# LED-Board.net
KiCad netlist of a schematic drawn in EAGLE
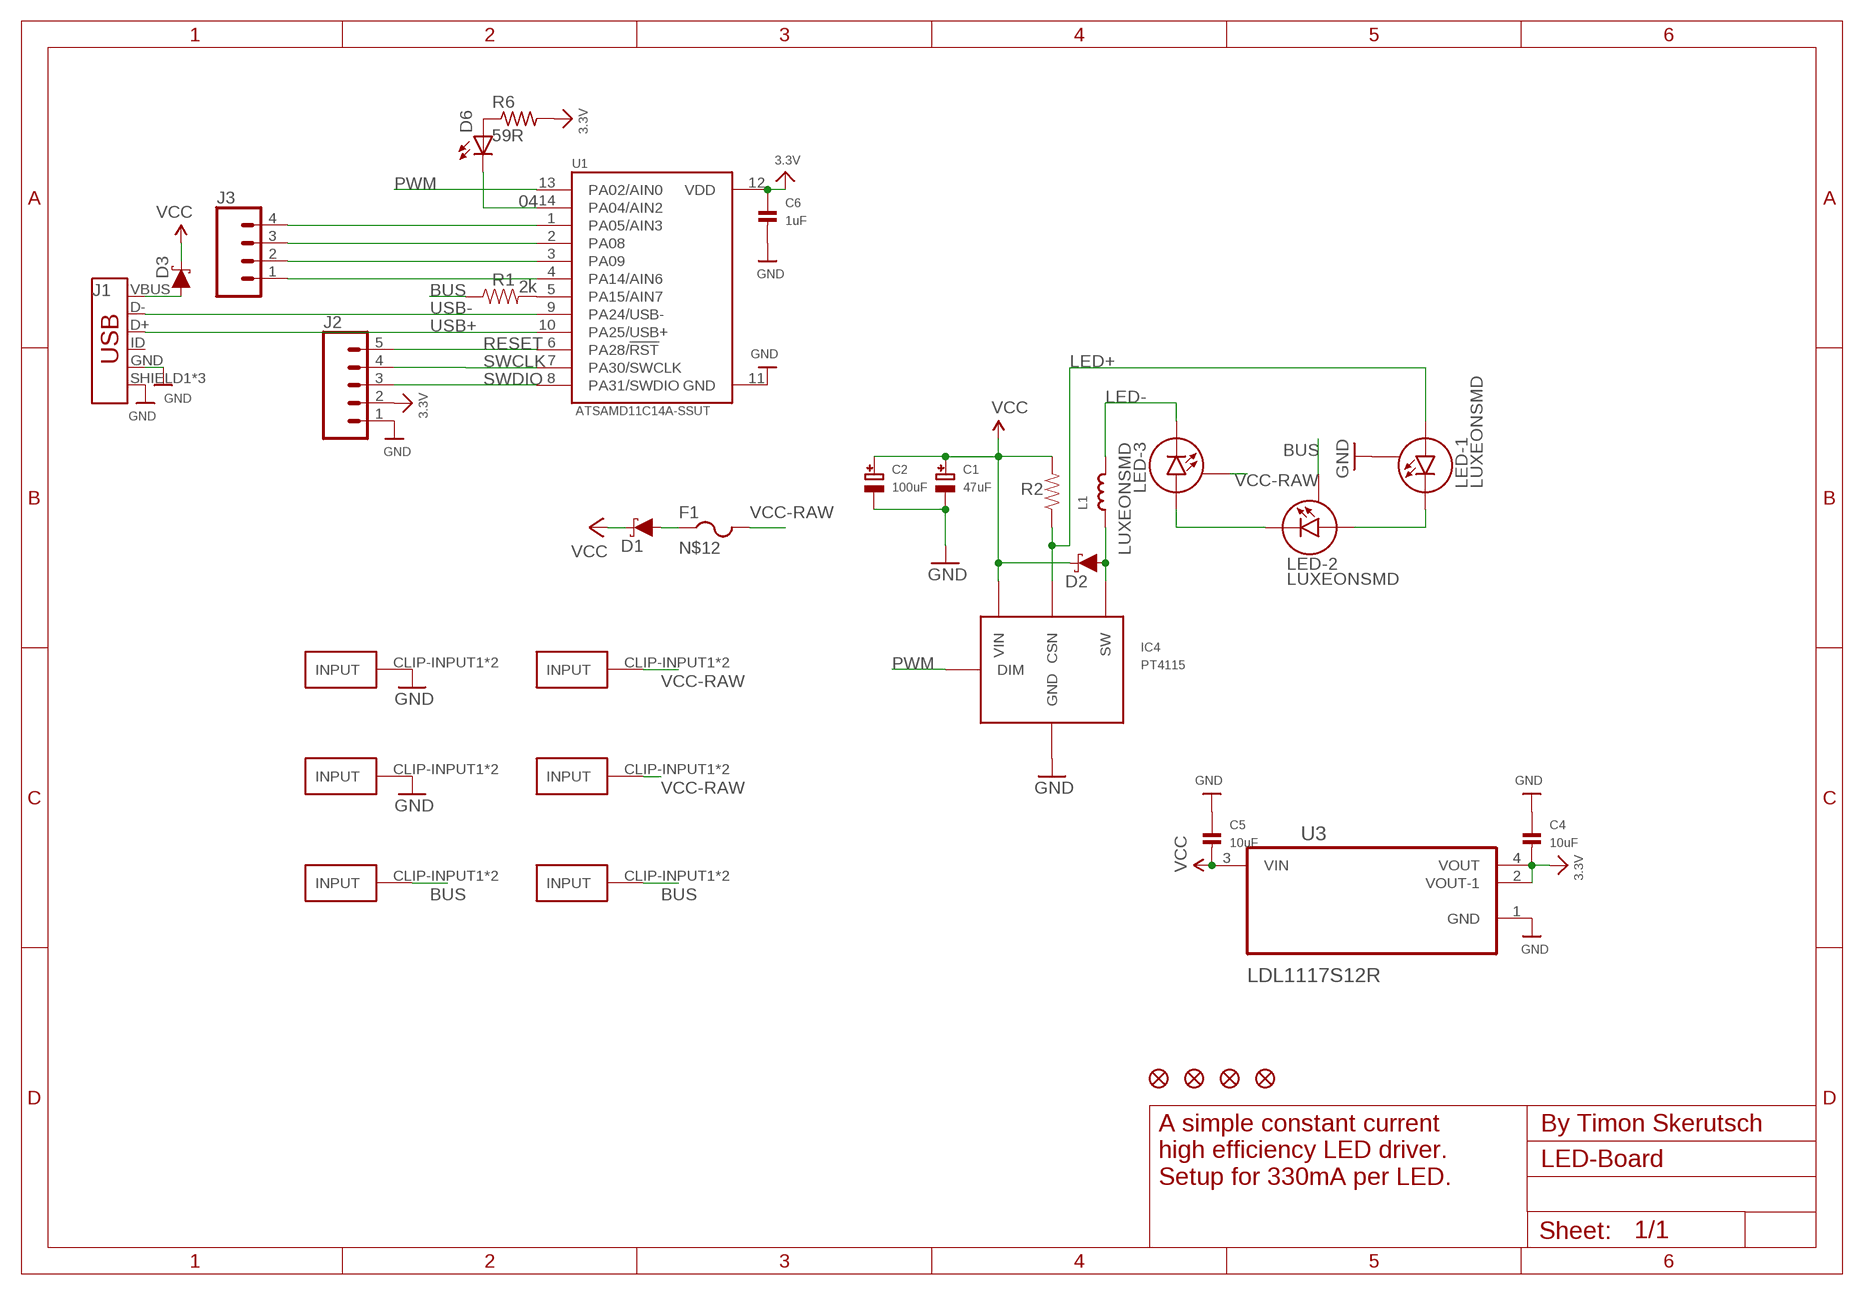
[diagram p0: schematic, sheet 1]

(export (version "E")
  (design (tool "Eeschema 10.0.6"))
  (components
    (comp (ref "C1")
      (value "47uF")
      (footprint "eagle-import:PANASONIC_D")
      (libsource (lib "eagle-import") (part "CAP_ELECTROLYTICPANASONIC_D"))
    )
    (comp (ref "C2")
      (value "100uF")
      (footprint "eagle-import:PANASONIC_D")
      (libsource (lib "eagle-import") (part "CAP_ELECTROLYTICPANASONIC_D"))
    )
    (comp (ref "C4")
      (value "10uF")
      (footprint "eagle-import:0805")
      (libsource (lib "eagle-import") (part "CAP_CERAMIC0805"))
    )
    (comp (ref "C5")
      (value "10uF")
      (footprint "eagle-import:0603")
      (libsource (lib "eagle-import") (part "CAP_CERAMIC0603"))
    )
    (comp (ref "C6")
      (value "1uF")
      (footprint "eagle-import:0603")
      (libsource (lib "eagle-import") (part "CAP_CERAMIC0603"))
    )
    (comp (ref "D1")
      (value "3A/40V/500mV")
      (footprint "eagle-import:SMA-DIODE")
      (libsource (lib "eagle-import") (part "DIODE-SCHOTTKY-B340A"))
    )
    (comp (ref "D2")
      (value "3A/40V/500mV")
      (footprint "eagle-import:SMA-DIODE")
      (libsource (lib "eagle-import") (part "DIODE-SCHOTTKY-B340A"))
    )
    (comp (ref "D3")
      (value "3A/40V/500mV")
      (footprint "eagle-import:SMA-DIODE")
      (libsource (lib "eagle-import") (part "DIODE-SCHOTTKY-B340A"))
    )
    (comp (ref "D6")
      (value "LEDCHIPLED_0805")
      (footprint "eagle-import:CHIPLED_0805")
      (libsource (lib "eagle-import") (part "LEDCHIPLED_0805"))
    )
    (comp (ref "F1")
      (value "TLC-MSMD110/24")
      (footprint "eagle-import:1812")
      (libsource (lib "eagle-import") (part "PTCFUSE-1812"))
    )
    (comp (ref "FD1")
      (value "FIDUCIAL1X2")
      (footprint "eagle-import:FIDUCIAL-1X2")
      (libsource (lib "eagle-import") (part "FIDUCIAL1X2"))
    )
    (comp (ref "FD2")
      (value "FIDUCIAL1X2")
      (footprint "eagle-import:FIDUCIAL-1X2")
      (libsource (lib "eagle-import") (part "FIDUCIAL1X2"))
    )
    (comp (ref "FD3")
      (value "FIDUCIAL1X2")
      (footprint "eagle-import:FIDUCIAL-1X2")
      (libsource (lib "eagle-import") (part "FIDUCIAL1X2"))
    )
    (comp (ref "FD4")
      (value "FIDUCIAL1X2")
      (footprint "eagle-import:FIDUCIAL-1X2")
      (libsource (lib "eagle-import") (part "FIDUCIAL1X2"))
    )
    (comp (ref "GND-CLIP")
      (value "FUSE-HOLDER-5X20MM")
      (footprint "eagle-import:FUSE-HOLDER-5X20MM")
      (libsource (lib "eagle-import") (part "FUSE-HOLDER-5X20MM"))
    )
    (comp (ref "GND-CLIP3")
      (value "FUSE-HOLDER-5X20MM")
      (footprint "eagle-import:FUSE-HOLDER-5X20MM")
      (libsource (lib "eagle-import") (part "FUSE-HOLDER-5X20MM"))
    )
    (comp (ref "IC4")
      (value "PT4115")
      (footprint "eagle-import:PT4115")
      (libsource (lib "eagle-import") (part "PT4115"))
    )
    (comp (ref "J1")
      (value "USB_MICRO-B_FEMALE-SMT")
      (footprint "eagle-import:USB-B-MICRO-SMD")
      (libsource (lib "eagle-import") (part "USB_MICRO-B_FEMALE-SMT"))
    )
    (comp (ref "J2")
      (value "CONN_05")
      (footprint "eagle-import:1X05")
      (libsource (lib "eagle-import") (part "CONN_05"))
    )
    (comp (ref "J3")
      (value "CONN_04")
      (footprint "eagle-import:1X04")
      (libsource (lib "eagle-import") (part "CONN_04"))
    )
    (comp (ref "L1")
      (value "INDUCTORTDK_VLC6045")
      (footprint "eagle-import:INDUCTOR_6X6MM_TDK_VLC6045")
      (libsource (lib "eagle-import") (part "INDUCTORTDK_VLC6045"))
    )
    (comp (ref "LED-1")
      (value "LUXEONSMD")
      (footprint "eagle-import:LUXEON")
      (libsource (lib "eagle-import") (part "LUXEONSMD"))
    )
    (comp (ref "LED-2")
      (value "LUXEONSMD")
      (footprint "eagle-import:LUXEON")
      (libsource (lib "eagle-import") (part "LUXEONSMD"))
    )
    (comp (ref "LED-3")
      (value "LUXEONSMD")
      (footprint "eagle-import:LUXEON")
      (libsource (lib "eagle-import") (part "LUXEONSMD"))
    )
    (comp (ref "PWM-CLIP")
      (value "FUSE-HOLDER-5X20MM")
      (footprint "eagle-import:FUSE-HOLDER-5X20MM")
      (libsource (lib "eagle-import") (part "FUSE-HOLDER-5X20MM"))
    )
    (comp (ref "PWM-CLIP1")
      (value "FUSE-HOLDER-5X20MM")
      (footprint "eagle-import:FUSE-HOLDER-5X20MM")
      (libsource (lib "eagle-import") (part "FUSE-HOLDER-5X20MM"))
    )
    (comp (ref "R1")
      (value "2k")
      (footprint "eagle-import:1206")
      (libsource (lib "eagle-import") (part "RESISTOR1206"))
    )
    (comp (ref "R2")
      (value "0.3")
      (footprint "eagle-import:1206")
      (libsource (lib "eagle-import") (part "RESISTOR1206"))
    )
    (comp (ref "R6")
      (value "59R")
      (footprint "eagle-import:R0805")
      (libsource (lib "eagle-import") (part "R-US_R0805"))
    )
    (comp (ref "U1")
      (value "ATSAMD11C14A-SSUT")
      (footprint "eagle-import:SOIC127P600X160-14N")
      (fields (field (name "MF") "Microchip"))
      (libsource (lib "eagle-import") (part "ATSAMD11C14A-SSUT"))
    )
    (comp (ref "U3")
      (value "LDL1117S12R")
      (footprint "eagle-import:SOT230P700X180-4N")
      (fields (field (name "MF") "STMicroelectronics"))
      (libsource (lib "eagle-import") (part "LDL1117S12R"))
    )
    (comp (ref "VCC-CLIP")
      (value "FUSE-HOLDER-5X20MM")
      (footprint "eagle-import:FUSE-HOLDER-5X20MM")
      (libsource (lib "eagle-import") (part "FUSE-HOLDER-5X20MM"))
    )
    (comp (ref "VCC-CLIP3")
      (value "FUSE-HOLDER-5X20MM")
      (footprint "eagle-import:FUSE-HOLDER-5X20MM")
      (libsource (lib "eagle-import") (part "FUSE-HOLDER-5X20MM"))
    )
  )
  (nets
    (net (code "1") (name "/04") (class "Default")
      (node (ref "D6") (pin "C") (pinfunction "C_C") (pintype "passive"))
      (node (ref "U1") (pin "14") (pinfunction "PA04/AIN2_14") (pintype "bidirectional"))
    )
    (net (code "2") (name "/BUS") (class "Default")
      (node (ref "LED-2") (pin "S") (pinfunction "S_S") (pintype "bidirectional"))
      (node (ref "PWM-CLIP") (pin "CLIP-INPUT1") (pinfunction "INPUT_CLIP-INPUT1") (pintype "bidirectional"))
      (node (ref "PWM-CLIP") (pin "CLIP-INPUT2") (pinfunction "INPUT_CLIP-INPUT2") (pintype "bidirectional"))
      (node (ref "PWM-CLIP1") (pin "CLIP-INPUT1") (pinfunction "INPUT_CLIP-INPUT1") (pintype "bidirectional"))
      (node (ref "PWM-CLIP1") (pin "CLIP-INPUT2") (pinfunction "INPUT_CLIP-INPUT2") (pintype "bidirectional"))
      (node (ref "R1") (pin "1") (pinfunction "1_1") (pintype "passive"))
    )
    (net (code "3") (name "/LED+") (class "Default")
      (node (ref "IC4") (pin "4") (pinfunction "CSN_4") (pintype "bidirectional"))
      (node (ref "LED-1") (pin "A") (pinfunction "A_A") (pintype "passive"))
      (node (ref "R2") (pin "1") (pinfunction "1_1") (pintype "passive"))
    )
    (net (code "4") (name "/LED-") (class "Default")
      (node (ref "L1") (pin "P$2") (pinfunction "2_P$2") (pintype "passive"))
      (node (ref "LED-3") (pin "C") (pinfunction "C_C") (pintype "passive"))
    )
    (net (code "5") (name "/N$12") (class "Default")
      (node (ref "D1") (pin "A") (pinfunction "A_A") (pintype "passive"))
      (node (ref "F1") (pin "1") (pinfunction "1_1") (pintype "passive"))
    )
    (net (code "6") (name "/PWM") (class "Default")
      (node (ref "IC4") (pin "3") (pinfunction "DIM_3") (pintype "bidirectional"))
      (node (ref "U1") (pin "13") (pinfunction "PA02/AIN0_13") (pintype "bidirectional"))
    )
    (net (code "7") (name "/RESET") (class "Default")
      (node (ref "J2") (pin "5") (pinfunction "5_5") (pintype "passive"))
      (node (ref "U1") (pin "6") (pinfunction "PA28/~{RST}_6") (pintype "bidirectional"))
    )
    (net (code "8") (name "/SWCLK") (class "Default")
      (node (ref "J2") (pin "4") (pinfunction "4_4") (pintype "passive"))
      (node (ref "U1") (pin "7") (pinfunction "PA30/SWCLK_7") (pintype "bidirectional"))
    )
    (net (code "9") (name "/SWDIO") (class "Default")
      (node (ref "J2") (pin "3") (pinfunction "3_3") (pintype "passive"))
      (node (ref "U1") (pin "8") (pinfunction "PA31/SWDIO_8") (pintype "bidirectional"))
    )
    (net (code "10") (name "/USB+") (class "Default")
      (node (ref "J1") (pin "D+") (pinfunction "D+_D+") (pintype "bidirectional"))
      (node (ref "U1") (pin "10") (pinfunction "PA25/USB+_10") (pintype "bidirectional"))
    )
    (net (code "11") (name "/USB-") (class "Default")
      (node (ref "J1") (pin "D-") (pinfunction "D-_D-") (pintype "bidirectional"))
      (node (ref "U1") (pin "9") (pinfunction "PA24/USB-_9") (pintype "bidirectional"))
    )
    (net (code "12") (name "/VCC-RAW") (class "Default")
      (node (ref "F1") (pin "2") (pinfunction "2_2") (pintype "passive"))
      (node (ref "LED-3") (pin "S") (pinfunction "S_S") (pintype "bidirectional"))
      (node (ref "VCC-CLIP") (pin "CLIP-INPUT1") (pinfunction "INPUT_CLIP-INPUT1") (pintype "bidirectional"))
      (node (ref "VCC-CLIP") (pin "CLIP-INPUT2") (pinfunction "INPUT_CLIP-INPUT2") (pintype "bidirectional"))
      (node (ref "VCC-CLIP3") (pin "CLIP-INPUT1") (pinfunction "INPUT_CLIP-INPUT1") (pintype "bidirectional"))
      (node (ref "VCC-CLIP3") (pin "CLIP-INPUT2") (pinfunction "INPUT_CLIP-INPUT2") (pintype "bidirectional"))
    )
    (net (code "13") (name "3.3V") (class "Default")
      (node (ref "C4") (pin "2") (pinfunction "P$2_2") (pintype "passive"))
      (node (ref "C6") (pin "1") (pinfunction "P$1_1") (pintype "passive"))
      (node (ref "J2") (pin "2") (pinfunction "2_2") (pintype "passive"))
      (node (ref "R6") (pin "2") (pinfunction "2_2") (pintype "passive"))
      (node (ref "U1") (pin "12") (pinfunction "VDD_12") (pintype "power_in"))
      (node (ref "U3") (pin "2") (pinfunction "VOUT-1_2") (pintype "output"))
      (node (ref "U3") (pin "4") (pinfunction "VOUT_4") (pintype "output"))
    )
    (net (code "14") (name "GND") (class "Default")
      (node (ref "C1") (pin "-") (pinfunction "-_-") (pintype "passive"))
      (node (ref "C2") (pin "-") (pinfunction "-_-") (pintype "passive"))
      (node (ref "C4") (pin "1") (pinfunction "P$1_1") (pintype "passive"))
      (node (ref "C5") (pin "1") (pinfunction "P$1_1") (pintype "passive"))
      (node (ref "C6") (pin "2") (pinfunction "P$2_2") (pintype "passive"))
      (node (ref "GND-CLIP") (pin "CLIP-INPUT1") (pinfunction "INPUT_CLIP-INPUT1") (pintype "bidirectional"))
      (node (ref "GND-CLIP") (pin "CLIP-INPUT2") (pinfunction "INPUT_CLIP-INPUT2") (pintype "bidirectional"))
      (node (ref "GND-CLIP3") (pin "CLIP-INPUT1") (pinfunction "INPUT_CLIP-INPUT1") (pintype "bidirectional"))
      (node (ref "GND-CLIP3") (pin "CLIP-INPUT2") (pinfunction "INPUT_CLIP-INPUT2") (pintype "bidirectional"))
      (node (ref "IC4") (pin "2") (pinfunction "GND_2") (pintype "power_in"))
      (node (ref "IC4") (pin "2A") (pinfunction "GND_2A") (pintype "power_in"))
      (node (ref "J1") (pin "GND") (pinfunction "GND_GND") (pintype "power_in"))
      (node (ref "J1") (pin "SHIELD1") (pinfunction "SHIELD_SHIELD1") (pintype "bidirectional"))
      (node (ref "J1") (pin "SHIELD2") (pinfunction "SHIELD_SHIELD2") (pintype "bidirectional"))
      (node (ref "J1") (pin "SHIELD3") (pinfunction "SHIELD_SHIELD3") (pintype "bidirectional"))
      (node (ref "J2") (pin "1") (pinfunction "1_1") (pintype "passive"))
      (node (ref "LED-1") (pin "S") (pinfunction "S_S") (pintype "bidirectional"))
      (node (ref "U1") (pin "11") (pinfunction "GND_11") (pintype "power_in"))
      (node (ref "U3") (pin "1") (pinfunction "GND_1") (pintype "power_in"))
    )
    (net (code "15") (name "Net-(D3-PadA)") (class "Default")
      (node (ref "D3") (pin "A") (pinfunction "A_A") (pintype "passive"))
      (node (ref "J1") (pin "VBUS") (pinfunction "VBUS_VBUS") (pintype "power_in"))
    )
    (net (code "16") (name "Net-(D6-PadA)") (class "Default")
      (node (ref "D6") (pin "A") (pinfunction "A_A") (pintype "passive"))
      (node (ref "R6") (pin "1") (pinfunction "1_1") (pintype "passive"))
    )
    (net (code "17") (name "Net-(IC4-SW)") (class "Default")
      (node (ref "D2") (pin "A") (pinfunction "A_A") (pintype "passive"))
      (node (ref "IC4") (pin "1") (pinfunction "SW_1") (pintype "bidirectional"))
      (node (ref "L1") (pin "P$1") (pinfunction "1_P$1") (pintype "passive"))
    )
    (net (code "18") (name "Net-(LED-1-PadC)") (class "Default")
      (node (ref "LED-1") (pin "C") (pinfunction "C_C") (pintype "passive"))
      (node (ref "LED-2") (pin "A") (pinfunction "A_A") (pintype "passive"))
    )
    (net (code "19") (name "Net-(LED-2-PadC)") (class "Default")
      (node (ref "LED-2") (pin "C") (pinfunction "C_C") (pintype "passive"))
      (node (ref "LED-3") (pin "A") (pinfunction "A_A") (pintype "passive"))
    )
    (net (code "20") (name "Net-(U1-PA05{slash}AIN3)") (class "Default")
      (node (ref "J3") (pin "4") (pinfunction "4_4") (pintype "passive"))
      (node (ref "U1") (pin "1") (pinfunction "PA05/AIN3_1") (pintype "bidirectional"))
    )
    (net (code "21") (name "Net-(U1-PA08)") (class "Default")
      (node (ref "J3") (pin "3") (pinfunction "3_3") (pintype "passive"))
      (node (ref "U1") (pin "2") (pinfunction "PA08_2") (pintype "bidirectional"))
    )
    (net (code "22") (name "Net-(U1-PA09)") (class "Default")
      (node (ref "J3") (pin "2") (pinfunction "2_2") (pintype "passive"))
      (node (ref "U1") (pin "3") (pinfunction "PA09_3") (pintype "bidirectional"))
    )
    (net (code "23") (name "Net-(U1-PA14{slash}AIN6)") (class "Default")
      (node (ref "J3") (pin "1") (pinfunction "1_1") (pintype "passive"))
      (node (ref "U1") (pin "4") (pinfunction "PA14/AIN6_4") (pintype "bidirectional"))
    )
    (net (code "24") (name "Net-(U1-PA15{slash}AIN7)") (class "Default")
      (node (ref "R1") (pin "2") (pinfunction "2_2") (pintype "passive"))
      (node (ref "U1") (pin "5") (pinfunction "PA15/AIN7_5") (pintype "bidirectional"))
    )
    (net (code "25") (name "VCC") (class "Default")
      (node (ref "C1") (pin "+") (pinfunction "+_+") (pintype "passive"))
      (node (ref "C2") (pin "+") (pinfunction "+_+") (pintype "passive"))
      (node (ref "C5") (pin "2") (pinfunction "P$2_2") (pintype "passive"))
      (node (ref "D1") (pin "C") (pinfunction "C_C") (pintype "passive"))
      (node (ref "D2") (pin "C") (pinfunction "C_C") (pintype "passive"))
      (node (ref "D3") (pin "C") (pinfunction "C_C") (pintype "passive"))
      (node (ref "IC4") (pin "5") (pinfunction "VIN_5") (pintype "bidirectional"))
      (node (ref "R2") (pin "2") (pinfunction "2_2") (pintype "passive"))
      (node (ref "U3") (pin "3") (pinfunction "VIN_3") (pintype "input"))
    )
    (net (code "26") (name "unconnected-(J1-PadID)") (class "Default")
      (node (ref "J1") (pin "ID") (pinfunction "ID_ID") (pintype "bidirectional"))
    )
  )
)
